# CV2018-DIFFx1.net
KiCad netlist of a schematic drawn in Altium Designer
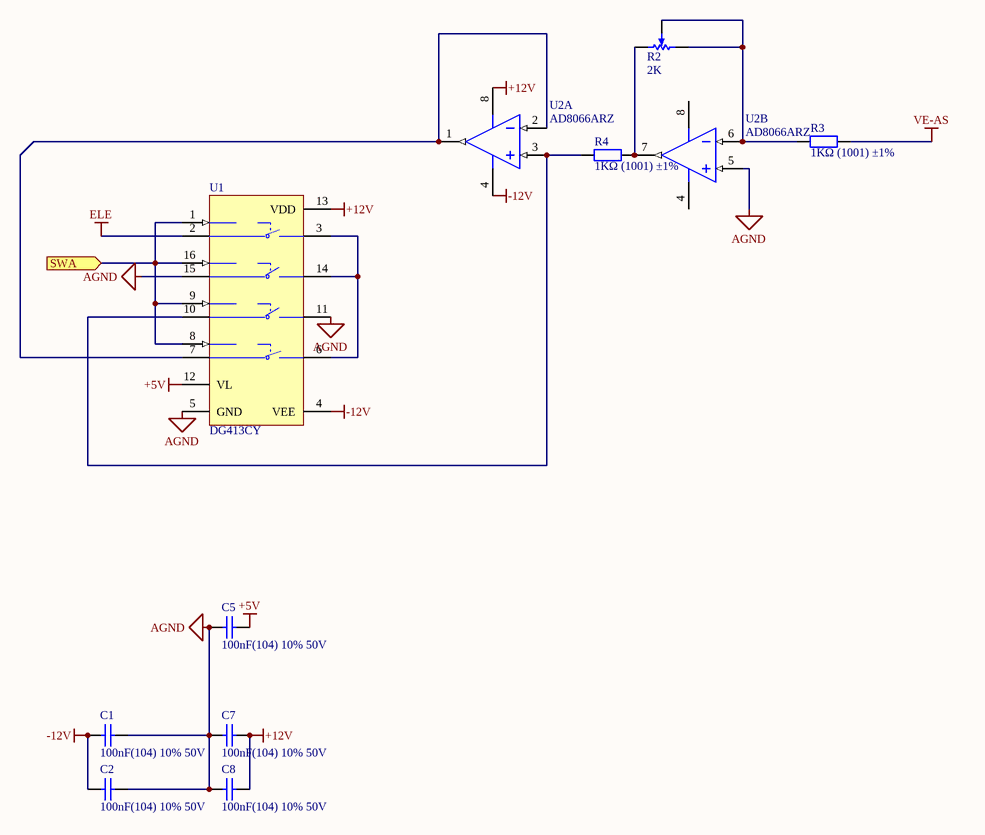
[diagram p0: CV2018-DIFFx1.SchDoc]

(export (version "E")
  (design (tool "Eeschema 10.0.6"))
  (components
    (comp (ref "C1")
      (value "100nF(104) 10% 50V")
      (footprint "LC-0805_C")
      (description "贴片电容")
      (libsource (lib "Miscellaneous Devices LC") (part "0805 100nF(104) 10% 50V"))
    )
    (comp (ref "C2")
      (value "100nF(104) 10% 50V")
      (footprint "LC-0805_C")
      (description "贴片电容")
      (libsource (lib "Miscellaneous Devices LC") (part "0805 100nF(104) 10% 50V"))
    )
    (comp (ref "C5")
      (value "100nF(104) 10% 50V")
      (footprint "LC-0805_C")
      (description "贴片电容")
      (libsource (lib "Miscellaneous Devices LC") (part "0805 100nF(104) 10% 50V"))
    )
    (comp (ref "C7")
      (value "100nF(104) 10% 50V")
      (footprint "LC-0805_C")
      (description "贴片电容")
      (libsource (lib "Miscellaneous Devices LC") (part "0805 100nF(104) 10% 50V"))
    )
    (comp (ref "C8")
      (value "100nF(104) 10% 50V")
      (footprint "LC-0805_C")
      (description "贴片电容")
      (libsource (lib "Miscellaneous Devices LC") (part "0805 100nF(104) 10% 50V"))
    )
    (comp (ref "R2")
      (value "2K")
      (footprint "POT4MM-2")
      (description "Square Trimming Potentiometer")
      (fields (field (name "PUBLISHER") "Altium Limited"))
      (libsource (lib "Miscellaneous Devices") (part "RPot SM"))
    )
    (comp (ref "R3")
      (value "1KΩ (1001) ±1%")
      (footprint "LC-0805_R")
      (description "贴片电阻")
      (libsource (lib "Miscellaneous Devices LC") (part "0805 1KΩ (1001) 1%"))
    )
    (comp (ref "R4")
      (value "1KΩ (1001) ±1%")
      (footprint "LC-0805_R")
      (description "贴片电阻")
      (libsource (lib "Miscellaneous Devices LC") (part "0805 1KΩ (1001) 1%"))
    )
    (comp (ref "U1")
      (value "DG413CY")
      (footprint "NSO16_N")
      (description "Improved, Quad, SPST Analog Switches")
      (fields (field (name "PUBLISHER") "Altium Limited"))
      (libsource (lib "Maxim Logic Switch") (part "DG413CY"))
    )
    (comp (ref "U2")
      (value "AD8066ARZ")
      (footprint "ADI-R-8_N")
      (fields (field (name "GENERIC PART NUMBER") "AD8066") (field (name "MANUFACTURER") "Analog Devices"))
      (libsource (lib "Analog Devices Operational Amplifiers") (part "AD8066ARZ"))
    )
  )
  (nets
    (net (code "1") (name "+5V") (class "Default")
      (node (ref "C5") (pin "2") (pinfunction "2_2") (pintype "passive"))
      (node (ref "U1") (pin "12") (pinfunction "VL_12") (pintype "power_in"))
    )
    (net (code "2") (name "+12V") (class "Default")
      (node (ref "C7") (pin "2") (pinfunction "2_2") (pintype "passive"))
      (node (ref "C8") (pin "2") (pinfunction "2_2") (pintype "passive"))
      (node (ref "U1") (pin "13") (pinfunction "VDD_13") (pintype "power_in"))
      (node (ref "U2") (pin "8") (pinfunction "+VS_8") (pintype "power_in"))
    )
    (net (code "3") (name "-12V") (class "Default")
      (node (ref "C1") (pin "1") (pinfunction "1_1") (pintype "passive"))
      (node (ref "C2") (pin "1") (pinfunction "1_1") (pintype "passive"))
      (node (ref "U1") (pin "4") (pinfunction "VEE_4") (pintype "power_in"))
      (node (ref "U2") (pin "4") (pinfunction "-VS_4") (pintype "power_in"))
    )
    (net (code "4") (name "/SWA") (class "Default")
      (node (ref "U1") (pin "1") (pinfunction "IN1_1") (pintype "input"))
      (node (ref "U1") (pin "16") (pinfunction "IN2_16") (pintype "input"))
      (node (ref "U1") (pin "8") (pinfunction "IN_4_8") (pintype "input"))
      (node (ref "U1") (pin "9") (pinfunction "IN3_9") (pintype "input"))
    )
    (net (code "5") (name "AGND") (class "Default")
      (node (ref "C1") (pin "2") (pinfunction "2_2") (pintype "passive"))
      (node (ref "C2") (pin "2") (pinfunction "2_2") (pintype "passive"))
      (node (ref "C5") (pin "1") (pinfunction "1_1") (pintype "passive"))
      (node (ref "C7") (pin "1") (pinfunction "1_1") (pintype "passive"))
      (node (ref "C8") (pin "1") (pinfunction "1_1") (pintype "passive"))
      (node (ref "U1") (pin "11") (pinfunction "S3_11") (pintype "passive"))
      (node (ref "U1") (pin "15") (pinfunction "D2_15") (pintype "passive"))
      (node (ref "U1") (pin "5") (pinfunction "GND_5") (pintype "power_in"))
      (node (ref "U2") (pin "5") (pinfunction "+IN_2_5") (pintype "input"))
    )
    (net (code "6") (name "ELE") (class "Default")
      (node (ref "U1") (pin "2") (pinfunction "D1_2") (pintype "passive"))
    )
    (net (code "7") (name "Net-(R2-+)") (class "Default")
      (node (ref "R2") (pin "CW") (pinfunction "+_CW") (pintype "passive"))
      (node (ref "R4") (pin "2") (pinfunction "2_2") (pintype "passive"))
      (node (ref "U2") (pin "7") (pinfunction "VOUT_2_7") (pintype "output"))
    )
    (net (code "8") (name "Net-(R2--)") (class "Default")
      (node (ref "R2") (pin "CCW") (pinfunction "-_CCW") (pintype "passive"))
      (node (ref "R2") (pin "W") (pinfunction "W_W") (pintype "passive"))
      (node (ref "R3") (pin "1") (pinfunction "1_1") (pintype "passive"))
      (node (ref "U2") (pin "6") (pinfunction "-IN_2_6") (pintype "input"))
    )
    (net (code "9") (name "Net-(U1-D3)") (class "Default")
      (node (ref "R4") (pin "1") (pinfunction "1_1") (pintype "passive"))
      (node (ref "U1") (pin "10") (pinfunction "D3_10") (pintype "passive"))
      (node (ref "U2") (pin "3") (pinfunction "+IN_1_3") (pintype "input"))
    )
    (net (code "10") (name "Net-(U1-D4)") (class "Default")
      (node (ref "U1") (pin "7") (pinfunction "D4_7") (pintype "passive"))
      (node (ref "U2") (pin "1") (pinfunction "VOUT_1_1") (pintype "output"))
      (node (ref "U2") (pin "2") (pinfunction "-IN_1_2") (pintype "input"))
    )
    (net (code "11") (name "Net-(U1-S1)") (class "Default")
      (node (ref "U1") (pin "14") (pinfunction "S2_14") (pintype "passive"))
      (node (ref "U1") (pin "3") (pinfunction "S1_3") (pintype "passive"))
      (node (ref "U1") (pin "6") (pinfunction "S4_6") (pintype "passive"))
    )
    (net (code "12") (name "VE-AS") (class "Default")
      (node (ref "R3") (pin "2") (pinfunction "2_2") (pintype "passive"))
    )
    (net (code "13") (name "unconnected-(U2B-+VS-Pad8)") (class "Default")
      (node (ref "U2") (pin "8") (pinfunction "+VS_8") (pintype "power_in"))
    )
    (net (code "14") (name "unconnected-(U2B--VS-Pad4)") (class "Default")
      (node (ref "U2") (pin "4") (pinfunction "-VS_4") (pintype "power_in"))
    )
  )
)
